# 3_SDRAM_Memories.net
KiCad netlist of a schematic drawn in Altium Designer
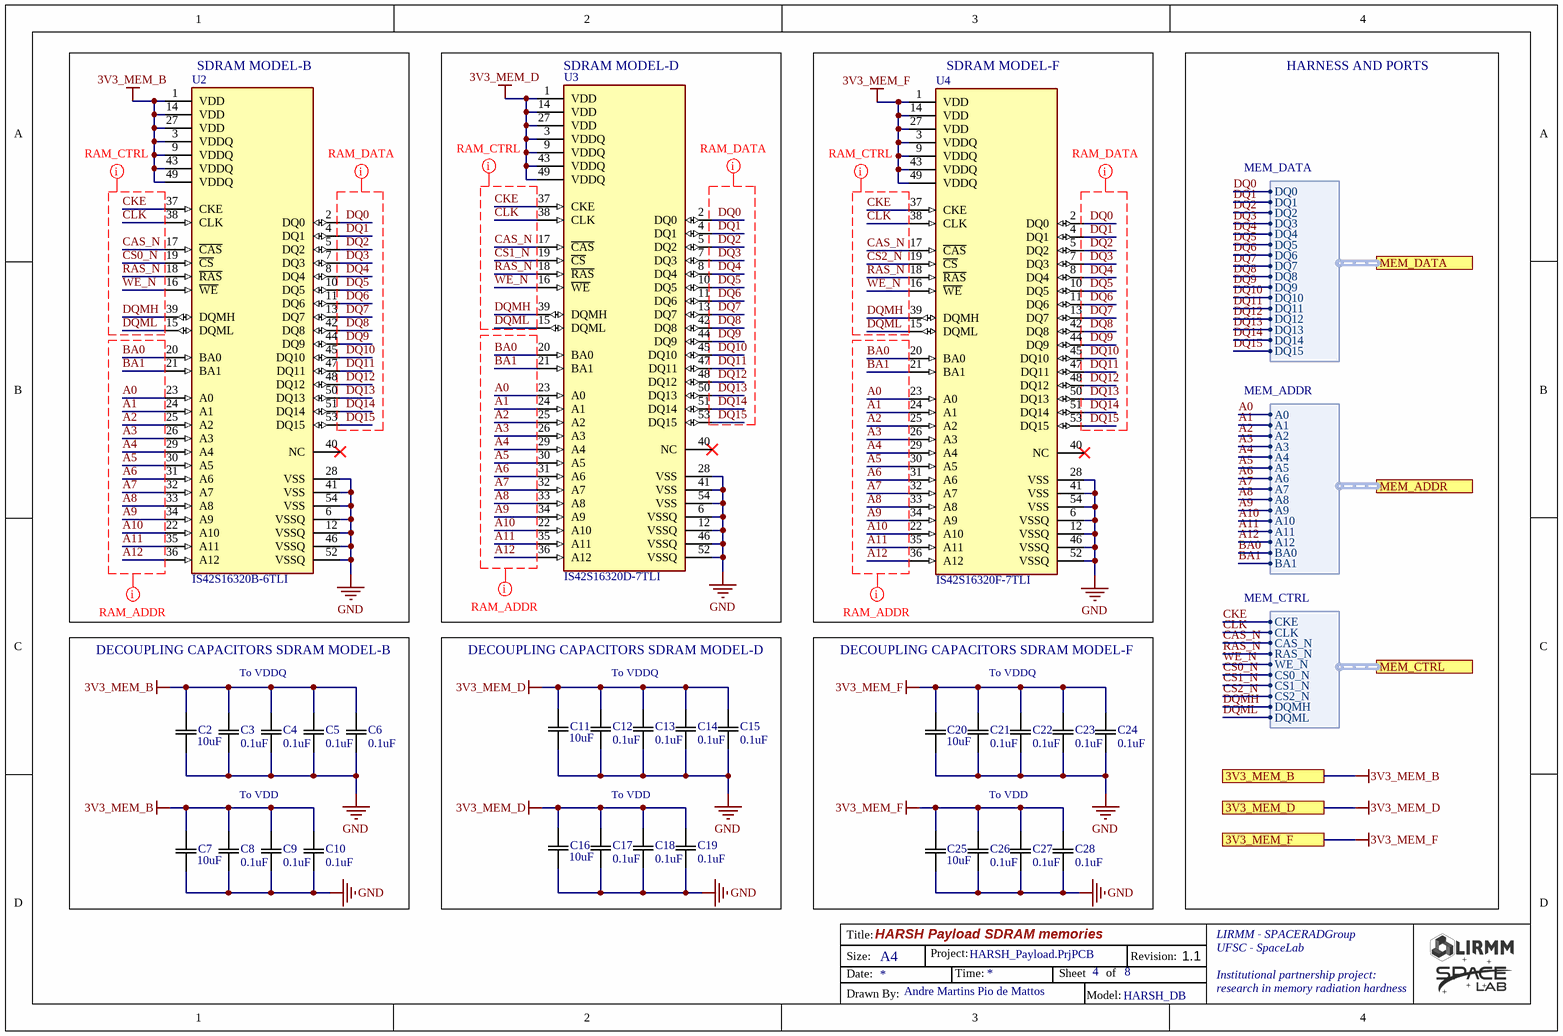
[diagram p0: 3_SDRAM_Memories.SchDoc]

(export (version "E")
  (design (tool "Eeschema 10.0.6"))
  (components
    (comp (ref "C2")
      (value "10uF")
      (footprint "DONE_C0603")
      (description "CAP CER 10uF 16V 0603 X5R")
      (fields
        (field (name "PARTNUMBER") "GRM188R61C106KAALD")
        (field (name "MANUFACTURER") "Murata")
        (field (name "CAPACITANCE") "10uF")
      )
      (libsource (lib "HARSH_Payload_SchLib") (part "DONE_CAP_10uF_0603_X5R"))
    )
    (comp (ref "C3")
      (value "100nF/50V")
      (footprint "DONE_C0603")
      (description "CAP CER 100nF 50V 0603 10%")
      (fields
        (field (name "PARTNUMBER") "C0603C104K5RAC3121")
        (field (name "MANUFACTURER") "Yageo")
        (field (name "CAPACITANCE") "0.1uF")
      )
      (libsource (lib "HARSH_Payload_SchLib") (part "DONE_CAP_0.1uF_0603_X7R"))
    )
    (comp (ref "C4")
      (value "100nF/50V")
      (footprint "DONE_C0603")
      (description "CAP CER 100nF 50V 0603 10%")
      (fields
        (field (name "PARTNUMBER") "C0603C104K5RAC3121")
        (field (name "MANUFACTURER") "Yageo")
        (field (name "CAPACITANCE") "0.1uF")
      )
      (libsource (lib "HARSH_Payload_SchLib") (part "DONE_CAP_0.1uF_0603_X7R"))
    )
    (comp (ref "C5")
      (value "100nF/50V")
      (footprint "DONE_C0603")
      (description "CAP CER 100nF 50V 0603 10%")
      (fields
        (field (name "PARTNUMBER") "C0603C104K5RAC3121")
        (field (name "MANUFACTURER") "Yageo")
        (field (name "CAPACITANCE") "0.1uF")
      )
      (libsource (lib "HARSH_Payload_SchLib") (part "DONE_CAP_0.1uF_0603_X7R"))
    )
    (comp (ref "C6")
      (value "100nF/50V")
      (footprint "DONE_C0603")
      (description "CAP CER 100nF 50V 0603 10%")
      (fields
        (field (name "PARTNUMBER") "C0603C104K5RAC3121")
        (field (name "MANUFACTURER") "Yageo")
        (field (name "CAPACITANCE") "0.1uF")
      )
      (libsource (lib "HARSH_Payload_SchLib") (part "DONE_CAP_0.1uF_0603_X7R"))
    )
    (comp (ref "C7")
      (value "10uF")
      (footprint "DONE_C0603")
      (description "CAP CER 10uF 16V 0603 X5R")
      (fields
        (field (name "PARTNUMBER") "GRM188R61C106KAALD")
        (field (name "MANUFACTURER") "Murata")
        (field (name "CAPACITANCE") "10uF")
      )
      (libsource (lib "HARSH_Payload_SchLib") (part "DONE_CAP_10uF_0603_X5R"))
    )
    (comp (ref "C8")
      (value "100nF/50V")
      (footprint "DONE_C0603")
      (description "CAP CER 100nF 50V 0603 10%")
      (fields
        (field (name "PARTNUMBER") "C0603C104K5RAC3121")
        (field (name "MANUFACTURER") "Yageo")
        (field (name "CAPACITANCE") "0.1uF")
      )
      (libsource (lib "HARSH_Payload_SchLib") (part "DONE_CAP_0.1uF_0603_X7R"))
    )
    (comp (ref "C9")
      (value "100nF/50V")
      (footprint "DONE_C0603")
      (description "CAP CER 100nF 50V 0603 10%")
      (fields
        (field (name "PARTNUMBER") "C0603C104K5RAC3121")
        (field (name "MANUFACTURER") "Yageo")
        (field (name "CAPACITANCE") "0.1uF")
      )
      (libsource (lib "HARSH_Payload_SchLib") (part "DONE_CAP_0.1uF_0603_X7R"))
    )
    (comp (ref "C10")
      (value "100nF/50V")
      (footprint "DONE_C0603")
      (description "CAP CER 100nF 50V 0603 10%")
      (fields
        (field (name "PARTNUMBER") "C0603C104K5RAC3121")
        (field (name "MANUFACTURER") "Yageo")
        (field (name "CAPACITANCE") "0.1uF")
      )
      (libsource (lib "HARSH_Payload_SchLib") (part "DONE_CAP_0.1uF_0603_X7R"))
    )
    (comp (ref "C11")
      (value "10uF")
      (footprint "DONE_C0603")
      (description "CAP CER 10uF 16V 0603 X5R")
      (fields
        (field (name "PARTNUMBER") "GRM188R61C106KAALD")
        (field (name "MANUFACTURER") "Murata")
        (field (name "CAPACITANCE") "10uF")
      )
      (libsource (lib "HARSH_Payload_SchLib") (part "DONE_CAP_10uF_0603_X5R"))
    )
    (comp (ref "C12")
      (value "100nF/50V")
      (footprint "DONE_C0603")
      (description "CAP CER 100nF 50V 0603 10%")
      (fields
        (field (name "PARTNUMBER") "C0603C104K5RAC3121")
        (field (name "MANUFACTURER") "Yageo")
        (field (name "CAPACITANCE") "0.1uF")
      )
      (libsource (lib "HARSH_Payload_SchLib") (part "DONE_CAP_0.1uF_0603_X7R"))
    )
    (comp (ref "C13")
      (value "100nF/50V")
      (footprint "DONE_C0603")
      (description "CAP CER 100nF 50V 0603 10%")
      (fields
        (field (name "PARTNUMBER") "C0603C104K5RAC3121")
        (field (name "MANUFACTURER") "Yageo")
        (field (name "CAPACITANCE") "0.1uF")
      )
      (libsource (lib "HARSH_Payload_SchLib") (part "DONE_CAP_0.1uF_0603_X7R"))
    )
    (comp (ref "C14")
      (value "100nF/50V")
      (footprint "DONE_C0603")
      (description "CAP CER 100nF 50V 0603 10%")
      (fields
        (field (name "PARTNUMBER") "C0603C104K5RAC3121")
        (field (name "MANUFACTURER") "Yageo")
        (field (name "CAPACITANCE") "0.1uF")
      )
      (libsource (lib "HARSH_Payload_SchLib") (part "DONE_CAP_0.1uF_0603_X7R"))
    )
    (comp (ref "C15")
      (value "100nF/50V")
      (footprint "DONE_C0603")
      (description "CAP CER 100nF 50V 0603 10%")
      (fields
        (field (name "PARTNUMBER") "C0603C104K5RAC3121")
        (field (name "MANUFACTURER") "Yageo")
        (field (name "CAPACITANCE") "0.1uF")
      )
      (libsource (lib "HARSH_Payload_SchLib") (part "DONE_CAP_0.1uF_0603_X7R"))
    )
    (comp (ref "C16")
      (value "10uF")
      (footprint "DONE_C0603")
      (description "CAP CER 10uF 16V 0603 X5R")
      (fields
        (field (name "PARTNUMBER") "GRM188R61C106KAALD")
        (field (name "MANUFACTURER") "Murata")
        (field (name "CAPACITANCE") "10uF")
      )
      (libsource (lib "HARSH_Payload_SchLib") (part "DONE_CAP_10uF_0603_X5R"))
    )
    (comp (ref "C17")
      (value "100nF/50V")
      (footprint "DONE_C0603")
      (description "CAP CER 100nF 50V 0603 10%")
      (fields
        (field (name "PARTNUMBER") "C0603C104K5RAC3121")
        (field (name "MANUFACTURER") "Yageo")
        (field (name "CAPACITANCE") "0.1uF")
      )
      (libsource (lib "HARSH_Payload_SchLib") (part "DONE_CAP_0.1uF_0603_X7R"))
    )
    (comp (ref "C18")
      (value "100nF/50V")
      (footprint "DONE_C0603")
      (description "CAP CER 100nF 50V 0603 10%")
      (fields
        (field (name "PARTNUMBER") "C0603C104K5RAC3121")
        (field (name "MANUFACTURER") "Yageo")
        (field (name "CAPACITANCE") "0.1uF")
      )
      (libsource (lib "HARSH_Payload_SchLib") (part "DONE_CAP_0.1uF_0603_X7R"))
    )
    (comp (ref "C19")
      (value "100nF/50V")
      (footprint "DONE_C0603")
      (description "CAP CER 100nF 50V 0603 10%")
      (fields
        (field (name "PARTNUMBER") "C0603C104K5RAC3121")
        (field (name "MANUFACTURER") "Yageo")
        (field (name "CAPACITANCE") "0.1uF")
      )
      (libsource (lib "HARSH_Payload_SchLib") (part "DONE_CAP_0.1uF_0603_X7R"))
    )
    (comp (ref "C20")
      (value "10uF")
      (footprint "DONE_C0603")
      (description "CAP CER 10uF 16V 0603 X5R")
      (fields
        (field (name "PARTNUMBER") "GRM188R61C106KAALD")
        (field (name "MANUFACTURER") "Murata")
        (field (name "CAPACITANCE") "10uF")
      )
      (libsource (lib "HARSH_Payload_SchLib") (part "DONE_CAP_10uF_0603_X5R"))
    )
    (comp (ref "C21")
      (value "100nF/50V")
      (footprint "DONE_C0603")
      (description "CAP CER 100nF 50V 0603 10%")
      (fields
        (field (name "PARTNUMBER") "C0603C104K5RAC3121")
        (field (name "MANUFACTURER") "Yageo")
        (field (name "CAPACITANCE") "0.1uF")
      )
      (libsource (lib "HARSH_Payload_SchLib") (part "DONE_CAP_0.1uF_0603_X7R"))
    )
    (comp (ref "C22")
      (value "100nF/50V")
      (footprint "DONE_C0603")
      (description "CAP CER 100nF 50V 0603 10%")
      (fields
        (field (name "PARTNUMBER") "C0603C104K5RAC3121")
        (field (name "MANUFACTURER") "Yageo")
        (field (name "CAPACITANCE") "0.1uF")
      )
      (libsource (lib "HARSH_Payload_SchLib") (part "DONE_CAP_0.1uF_0603_X7R"))
    )
    (comp (ref "C23")
      (value "100nF/50V")
      (footprint "DONE_C0603")
      (description "CAP CER 100nF 50V 0603 10%")
      (fields
        (field (name "PARTNUMBER") "C0603C104K5RAC3121")
        (field (name "MANUFACTURER") "Yageo")
        (field (name "CAPACITANCE") "0.1uF")
      )
      (libsource (lib "HARSH_Payload_SchLib") (part "DONE_CAP_0.1uF_0603_X7R"))
    )
    (comp (ref "C24")
      (value "100nF/50V")
      (footprint "DONE_C0603")
      (description "CAP CER 100nF 50V 0603 10%")
      (fields
        (field (name "PARTNUMBER") "C0603C104K5RAC3121")
        (field (name "MANUFACTURER") "Yageo")
        (field (name "CAPACITANCE") "0.1uF")
      )
      (libsource (lib "HARSH_Payload_SchLib") (part "DONE_CAP_0.1uF_0603_X7R"))
    )
    (comp (ref "C25")
      (value "10uF")
      (footprint "DONE_C0603")
      (description "CAP CER 10uF 16V 0603 X5R")
      (fields
        (field (name "PARTNUMBER") "GRM188R61C106KAALD")
        (field (name "MANUFACTURER") "Murata")
        (field (name "CAPACITANCE") "10uF")
      )
      (libsource (lib "HARSH_Payload_SchLib") (part "DONE_CAP_10uF_0603_X5R"))
    )
    (comp (ref "C26")
      (value "100nF/50V")
      (footprint "DONE_C0603")
      (description "CAP CER 100nF 50V 0603 10%")
      (fields
        (field (name "PARTNUMBER") "C0603C104K5RAC3121")
        (field (name "MANUFACTURER") "Yageo")
        (field (name "CAPACITANCE") "0.1uF")
      )
      (libsource (lib "HARSH_Payload_SchLib") (part "DONE_CAP_0.1uF_0603_X7R"))
    )
    (comp (ref "C27")
      (value "100nF/50V")
      (footprint "DONE_C0603")
      (description "CAP CER 100nF 50V 0603 10%")
      (fields
        (field (name "PARTNUMBER") "C0603C104K5RAC3121")
        (field (name "MANUFACTURER") "Yageo")
        (field (name "CAPACITANCE") "0.1uF")
      )
      (libsource (lib "HARSH_Payload_SchLib") (part "DONE_CAP_0.1uF_0603_X7R"))
    )
    (comp (ref "C28")
      (value "100nF/50V")
      (footprint "DONE_C0603")
      (description "CAP CER 100nF 50V 0603 10%")
      (fields
        (field (name "PARTNUMBER") "C0603C104K5RAC3121")
        (field (name "MANUFACTURER") "Yageo")
        (field (name "CAPACITANCE") "0.1uF")
      )
      (libsource (lib "HARSH_Payload_SchLib") (part "DONE_CAP_0.1uF_0603_X7R"))
    )
    (comp (ref "U2")
      (value "IS42S16320B-6TLI")
      (footprint "DONE_ISSI_MEM_TSOP_54")
      (description "DRAM 512M, 3.3V, SDRAM, 32Mx16, 143MHz, 54 pin TSOP II")
      (fields (field (name "PARTNUMBER") "IS42S16320B-6TLI"))
      (libsource (lib "HARSH_Payload_SchLib") (part "DONE_ISSI_MEM_MODEL_B"))
    )
    (comp (ref "U3")
      (value "IS42S16320D-7TLI")
      (footprint "DONE_ISSI_MEM_TSOP_54")
      (description "DRAM 512M, 3.3V, SDRAM, 32Mx16, 143MHz, 54 pin TSOP II")
      (fields (field (name "PARTNUMBER") "IS42S16320D-7TLI"))
      (libsource (lib "HARSH_Payload_SchLib") (part "DONE_ISSI_MEM_MODEL_D"))
    )
    (comp (ref "U4")
      (value "IS42S16320F-7TLI")
      (footprint "DONE_ISSI_MEM_TSOP_54")
      (description "DRAM 512M, 3.3V, SDRAM, 32Mx16, 143MHz, 54 pin TSOP II")
      (fields (field (name "PARTNUMBER") "IS42S16320F-7TLI"))
      (libsource (lib "HARSH_Payload_SchLib") (part "DONE_ISSI_MEM_MODEL_F"))
    )
  )
  (nets
    (net (code "4") (name "/A0") (class "Default")
      (node (ref "U2") (pin "23") (pinfunction "A0_23") (pintype "input"))
      (node (ref "U3") (pin "23") (pinfunction "A0_23") (pintype "input"))
      (node (ref "U4") (pin "23") (pinfunction "A0_23") (pintype "input"))
    )
    (net (code "5") (name "/A1") (class "Default")
      (node (ref "U2") (pin "24") (pinfunction "A1_24") (pintype "input"))
      (node (ref "U3") (pin "24") (pinfunction "A1_24") (pintype "input"))
      (node (ref "U4") (pin "24") (pinfunction "A1_24") (pintype "input"))
    )
    (net (code "6") (name "/A2") (class "Default")
      (node (ref "U2") (pin "25") (pinfunction "A2_25") (pintype "input"))
      (node (ref "U3") (pin "25") (pinfunction "A2_25") (pintype "input"))
      (node (ref "U4") (pin "25") (pinfunction "A2_25") (pintype "input"))
    )
    (net (code "7") (name "/A3") (class "Default")
      (node (ref "U2") (pin "26") (pinfunction "A3_26") (pintype "input"))
      (node (ref "U3") (pin "26") (pinfunction "A3_26") (pintype "input"))
      (node (ref "U4") (pin "26") (pinfunction "A3_26") (pintype "input"))
    )
    (net (code "8") (name "/A4") (class "Default")
      (node (ref "U2") (pin "29") (pinfunction "A4_29") (pintype "input"))
      (node (ref "U3") (pin "29") (pinfunction "A4_29") (pintype "input"))
      (node (ref "U4") (pin "29") (pinfunction "A4_29") (pintype "input"))
    )
    (net (code "9") (name "/A5") (class "Default")
      (node (ref "U2") (pin "30") (pinfunction "A5_30") (pintype "input"))
      (node (ref "U3") (pin "30") (pinfunction "A5_30") (pintype "input"))
      (node (ref "U4") (pin "30") (pinfunction "A5_30") (pintype "input"))
    )
    (net (code "10") (name "/A6") (class "Default")
      (node (ref "U2") (pin "31") (pinfunction "A6_31") (pintype "input"))
      (node (ref "U3") (pin "31") (pinfunction "A6_31") (pintype "input"))
      (node (ref "U4") (pin "31") (pinfunction "A6_31") (pintype "input"))
    )
    (net (code "11") (name "/A7") (class "Default")
      (node (ref "U2") (pin "32") (pinfunction "A7_32") (pintype "input"))
      (node (ref "U3") (pin "32") (pinfunction "A7_32") (pintype "input"))
      (node (ref "U4") (pin "32") (pinfunction "A7_32") (pintype "input"))
    )
    (net (code "12") (name "/A8") (class "Default")
      (node (ref "U2") (pin "33") (pinfunction "A8_33") (pintype "input"))
      (node (ref "U3") (pin "33") (pinfunction "A8_33") (pintype "input"))
      (node (ref "U4") (pin "33") (pinfunction "A8_33") (pintype "input"))
    )
    (net (code "13") (name "/A9") (class "Default")
      (node (ref "U2") (pin "34") (pinfunction "A9_34") (pintype "input"))
      (node (ref "U3") (pin "34") (pinfunction "A9_34") (pintype "input"))
      (node (ref "U4") (pin "34") (pinfunction "A9_34") (pintype "input"))
    )
    (net (code "14") (name "/A10") (class "Default")
      (node (ref "U2") (pin "22") (pinfunction "A10_22") (pintype "input"))
      (node (ref "U3") (pin "22") (pinfunction "A10_22") (pintype "input"))
      (node (ref "U4") (pin "22") (pinfunction "A10_22") (pintype "input"))
    )
    (net (code "15") (name "/A11") (class "Default")
      (node (ref "U2") (pin "35") (pinfunction "A11_35") (pintype "input"))
      (node (ref "U3") (pin "35") (pinfunction "A11_35") (pintype "input"))
      (node (ref "U4") (pin "35") (pinfunction "A11_35") (pintype "input"))
    )
    (net (code "16") (name "/A12") (class "Default")
      (node (ref "U2") (pin "36") (pinfunction "A12_36") (pintype "input"))
      (node (ref "U3") (pin "36") (pinfunction "A12_36") (pintype "input"))
      (node (ref "U4") (pin "36") (pinfunction "A12_36") (pintype "input"))
    )
    (net (code "17") (name "/BA0") (class "Default")
      (node (ref "U2") (pin "20") (pinfunction "BA0_20") (pintype "input"))
      (node (ref "U3") (pin "20") (pinfunction "BA0_20") (pintype "input"))
      (node (ref "U4") (pin "20") (pinfunction "BA0_20") (pintype "input"))
    )
    (net (code "18") (name "/BA1") (class "Default")
      (node (ref "U2") (pin "21") (pinfunction "BA1_21") (pintype "input"))
      (node (ref "U3") (pin "21") (pinfunction "BA1_21") (pintype "input"))
      (node (ref "U4") (pin "21") (pinfunction "BA1_21") (pintype "input"))
    )
    (net (code "19") (name "/CAS_N") (class "Default")
      (node (ref "U2") (pin "17") (pinfunction "~{CAS}_17") (pintype "input"))
      (node (ref "U3") (pin "17") (pinfunction "~{CAS}_17") (pintype "input"))
      (node (ref "U4") (pin "17") (pinfunction "~{CAS}_17") (pintype "input"))
    )
    (net (code "20") (name "/CKE") (class "Default")
      (node (ref "U2") (pin "37") (pinfunction "CKE_37") (pintype "input"))
      (node (ref "U3") (pin "37") (pinfunction "CKE_37") (pintype "input"))
      (node (ref "U4") (pin "37") (pinfunction "CKE_37") (pintype "input"))
    )
    (net (code "21") (name "/CLK") (class "Default")
      (node (ref "U2") (pin "38") (pinfunction "CLK_38") (pintype "input"))
      (node (ref "U3") (pin "38") (pinfunction "CLK_38") (pintype "input"))
      (node (ref "U4") (pin "38") (pinfunction "CLK_38") (pintype "input"))
    )
    (net (code "22") (name "/CS0_N") (class "Default")
      (node (ref "U2") (pin "19") (pinfunction "~{CS}_19") (pintype "input"))
    )
    (net (code "23") (name "/CS1_N") (class "Default")
      (node (ref "U3") (pin "19") (pinfunction "~{CS}_19") (pintype "input"))
    )
    (net (code "24") (name "/CS2_N") (class "Default")
      (node (ref "U4") (pin "19") (pinfunction "~{CS}_19") (pintype "input"))
    )
    (net (code "25") (name "/DQ0") (class "Default")
      (node (ref "U2") (pin "2") (pinfunction "DQ0_2") (pintype "bidirectional"))
      (node (ref "U3") (pin "2") (pinfunction "DQ0_2") (pintype "bidirectional"))
      (node (ref "U4") (pin "2") (pinfunction "DQ0_2") (pintype "bidirectional"))
    )
    (net (code "26") (name "/DQ1") (class "Default")
      (node (ref "U2") (pin "4") (pinfunction "DQ1_4") (pintype "bidirectional"))
      (node (ref "U3") (pin "4") (pinfunction "DQ1_4") (pintype "bidirectional"))
      (node (ref "U4") (pin "4") (pinfunction "DQ1_4") (pintype "bidirectional"))
    )
    (net (code "27") (name "/DQ2") (class "Default")
      (node (ref "U2") (pin "5") (pinfunction "DQ2_5") (pintype "bidirectional"))
      (node (ref "U3") (pin "5") (pinfunction "DQ2_5") (pintype "bidirectional"))
      (node (ref "U4") (pin "5") (pinfunction "DQ2_5") (pintype "bidirectional"))
    )
    (net (code "28") (name "/DQ3") (class "Default")
      (node (ref "U2") (pin "7") (pinfunction "DQ3_7") (pintype "bidirectional"))
      (node (ref "U3") (pin "7") (pinfunction "DQ3_7") (pintype "bidirectional"))
      (node (ref "U4") (pin "7") (pinfunction "DQ3_7") (pintype "bidirectional"))
    )
    (net (code "29") (name "/DQ4") (class "Default")
      (node (ref "U2") (pin "8") (pinfunction "DQ4_8") (pintype "bidirectional"))
      (node (ref "U3") (pin "8") (pinfunction "DQ4_8") (pintype "bidirectional"))
      (node (ref "U4") (pin "8") (pinfunction "DQ4_8") (pintype "bidirectional"))
    )
    (net (code "30") (name "/DQ5") (class "Default")
      (node (ref "U2") (pin "10") (pinfunction "DQ5_10") (pintype "bidirectional"))
      (node (ref "U3") (pin "10") (pinfunction "DQ5_10") (pintype "bidirectional"))
      (node (ref "U4") (pin "10") (pinfunction "DQ5_10") (pintype "bidirectional"))
    )
    (net (code "31") (name "/DQ6") (class "Default")
      (node (ref "U2") (pin "11") (pinfunction "DQ6_11") (pintype "bidirectional"))
      (node (ref "U3") (pin "11") (pinfunction "DQ6_11") (pintype "bidirectional"))
      (node (ref "U4") (pin "11") (pinfunction "DQ6_11") (pintype "bidirectional"))
    )
    (net (code "32") (name "/DQ7") (class "Default")
      (node (ref "U2") (pin "13") (pinfunction "DQ7_13") (pintype "bidirectional"))
      (node (ref "U3") (pin "13") (pinfunction "DQ7_13") (pintype "bidirectional"))
      (node (ref "U4") (pin "13") (pinfunction "DQ7_13") (pintype "bidirectional"))
    )
    (net (code "33") (name "/DQ8") (class "Default")
      (node (ref "U2") (pin "42") (pinfunction "DQ8_42") (pintype "bidirectional"))
      (node (ref "U3") (pin "42") (pinfunction "DQ8_42") (pintype "bidirectional"))
      (node (ref "U4") (pin "42") (pinfunction "DQ8_42") (pintype "bidirectional"))
    )
    (net (code "34") (name "/DQ9") (class "Default")
      (node (ref "U2") (pin "44") (pinfunction "DQ9_44") (pintype "bidirectional"))
      (node (ref "U3") (pin "44") (pinfunction "DQ9_44") (pintype "bidirectional"))
      (node (ref "U4") (pin "44") (pinfunction "DQ9_44") (pintype "bidirectional"))
    )
    (net (code "35") (name "/DQ10") (class "Default")
      (node (ref "U2") (pin "45") (pinfunction "DQ10_45") (pintype "bidirectional"))
      (node (ref "U3") (pin "45") (pinfunction "DQ10_45") (pintype "bidirectional"))
      (node (ref "U4") (pin "45") (pinfunction "DQ10_45") (pintype "bidirectional"))
    )
    (net (code "36") (name "/DQ11") (class "Default")
      (node (ref "U2") (pin "47") (pinfunction "DQ11_47") (pintype "bidirectional"))
      (node (ref "U3") (pin "47") (pinfunction "DQ11_47") (pintype "bidirectional"))
      (node (ref "U4") (pin "47") (pinfunction "DQ11_47") (pintype "bidirectional"))
    )
    (net (code "37") (name "/DQ12") (class "Default")
      (node (ref "U2") (pin "48") (pinfunction "DQ12_48") (pintype "bidirectional"))
      (node (ref "U3") (pin "48") (pinfunction "DQ12_48") (pintype "bidirectional"))
      (node (ref "U4") (pin "48") (pinfunction "DQ12_48") (pintype "bidirectional"))
    )
    (net (code "38") (name "/DQ13") (class "Default")
      (node (ref "U2") (pin "50") (pinfunction "DQ13_50") (pintype "bidirectional"))
      (node (ref "U3") (pin "50") (pinfunction "DQ13_50") (pintype "bidirectional"))
      (node (ref "U4") (pin "50") (pinfunction "DQ13_50") (pintype "bidirectional"))
    )
    (net (code "39") (name "/DQ14") (class "Default")
      (node (ref "U2") (pin "51") (pinfunction "DQ14_51") (pintype "bidirectional"))
      (node (ref "U3") (pin "51") (pinfunction "DQ14_51") (pintype "bidirectional"))
      (node (ref "U4") (pin "51") (pinfunction "DQ14_51") (pintype "bidirectional"))
    )
    (net (code "40") (name "/DQ15") (class "Default")
      (node (ref "U2") (pin "53") (pinfunction "DQ15_53") (pintype "bidirectional"))
      (node (ref "U3") (pin "53") (pinfunction "DQ15_53") (pintype "bidirectional"))
      (node (ref "U4") (pin "53") (pinfunction "DQ15_53") (pintype "bidirectional"))
    )
    (net (code "41") (name "/DQMH") (class "Default")
      (node (ref "U2") (pin "39") (pinfunction "DQMH_39") (pintype "bidirectional"))
      (node (ref "U3") (pin "39") (pinfunction "DQMH_39") (pintype "bidirectional"))
      (node (ref "U4") (pin "39") (pinfunction "DQMH_39") (pintype "bidirectional"))
    )
    (net (code "42") (name "/DQML") (class "Default")
      (node (ref "U2") (pin "15") (pinfunction "DQML_15") (pintype "bidirectional"))
      (node (ref "U3") (pin "15") (pinfunction "DQML_15") (pintype "bidirectional"))
      (node (ref "U4") (pin "15") (pinfunction "DQML_15") (pintype "bidirectional"))
    )
    (net (code "43") (name "/RAS_N") (class "Default")
      (node (ref "U2") (pin "18") (pinfunction "~{RAS}_18") (pintype "input"))
      (node (ref "U3") (pin "18") (pinfunction "~{RAS}_18") (pintype "input"))
      (node (ref "U4") (pin "18") (pinfunction "~{RAS}_18") (pintype "input"))
    )
    (net (code "44") (name "/WE_N") (class "Default")
      (node (ref "U2") (pin "16") (pinfunction "~{WE}_16") (pintype "input"))
      (node (ref "U3") (pin "16") (pinfunction "~{WE}_16") (pintype "input"))
      (node (ref "U4") (pin "16") (pinfunction "~{WE}_16") (pintype "input"))
    )
    (net (code "48") (name "3V3_MEM_B") (class "Default")
      (node (ref "C10") (pin "1") (pinfunction "1_1") (pintype "passive"))
      (node (ref "C2") (pin "1") (pinfunction "1_1") (pintype "passive"))
      (node (ref "C3") (pin "1") (pinfunction "1_1") (pintype "passive"))
      (node (ref "C4") (pin "1") (pinfunction "1_1") (pintype "passive"))
      (node (ref "C5") (pin "1") (pinfunction "1_1") (pintype "passive"))
      (node (ref "C6") (pin "1") (pinfunction "1_1") (pintype "passive"))
      (node (ref "C7") (pin "1") (pinfunction "1_1") (pintype "passive"))
      (node (ref "C8") (pin "1") (pinfunction "1_1") (pintype "passive"))
      (node (ref "C9") (pin "1") (pinfunction "1_1") (pintype "passive"))
      (node (ref "U2") (pin "1") (pinfunction "VDD_1") (pintype "power_in"))
      (node (ref "U2") (pin "14") (pinfunction "VDD_14") (pintype "power_in"))
      (node (ref "U2") (pin "27") (pinfunction "VDD_27") (pintype "power_in"))
      (node (ref "U2") (pin "3") (pinfunction "VDDQ_3") (pintype "power_in"))
      (node (ref "U2") (pin "43") (pinfunction "VDDQ_43") (pintype "power_in"))
      (node (ref "U2") (pin "49") (pinfunction "VDDQ_49") (pintype "power_in"))
      (node (ref "U2") (pin "9") (pinfunction "VDDQ_9") (pintype "power_in"))
    )
    (net (code "49") (name "3V3_MEM_D") (class "Default")
      (node (ref "C11") (pin "1") (pinfunction "1_1") (pintype "passive"))
      (node (ref "C12") (pin "1") (pinfunction "1_1") (pintype "passive"))
      (node (ref "C13") (pin "1") (pinfunction "1_1") (pintype "passive"))
      (node (ref "C14") (pin "1") (pinfunction "1_1") (pintype "passive"))
      (node (ref "C15") (pin "1") (pinfunction "1_1") (pintype "passive"))
      (node (ref "C16") (pin "1") (pinfunction "1_1") (pintype "passive"))
      (node (ref "C17") (pin "1") (pinfunction "1_1") (pintype "passive"))
      (node (ref "C18") (pin "1") (pinfunction "1_1") (pintype "passive"))
      (node (ref "C19") (pin "1") (pinfunction "1_1") (pintype "passive"))
      (node (ref "U3") (pin "1") (pinfunction "VDD_1") (pintype "power_in"))
      (node (ref "U3") (pin "14") (pinfunction "VDD_14") (pintype "power_in"))
      (node (ref "U3") (pin "27") (pinfunction "VDD_27") (pintype "power_in"))
      (node (ref "U3") (pin "3") (pinfunction "VDDQ_3") (pintype "power_in"))
      (node (ref "U3") (pin "43") (pinfunction "VDDQ_43") (pintype "power_in"))
      (node (ref "U3") (pin "49") (pinfunction "VDDQ_49") (pintype "power_in"))
      (node (ref "U3") (pin "9") (pinfunction "VDDQ_9") (pintype "power_in"))
    )
    (net (code "50") (name "3V3_MEM_F") (class "Default")
      (node (ref "C20") (pin "1") (pinfunction "1_1") (pintype "passive"))
      (node (ref "C21") (pin "1") (pinfunction "1_1") (pintype "passive"))
      (node (ref "C22") (pin "1") (pinfunction "1_1") (pintype "passive"))
      (node (ref "C23") (pin "1") (pinfunction "1_1") (pintype "passive"))
      (node (ref "C24") (pin "1") (pinfunction "1_1") (pintype "passive"))
      (node (ref "C25") (pin "1") (pinfunction "1_1") (pintype "passive"))
      (node (ref "C26") (pin "1") (pinfunction "1_1") (pintype "passive"))
      (node (ref "C27") (pin "1") (pinfunction "1_1") (pintype "passive"))
      (node (ref "C28") (pin "1") (pinfunction "1_1") (pintype "passive"))
      (node (ref "U4") (pin "1") (pinfunction "VDD_1") (pintype "power_in"))
      (node (ref "U4") (pin "14") (pinfunction "VDD_14") (pintype "power_in"))
      (node (ref "U4") (pin "27") (pinfunction "VDD_27") (pintype "power_in"))
      (node (ref "U4") (pin "3") (pinfunction "VDDQ_3") (pintype "power_in"))
      (node (ref "U4") (pin "43") (pinfunction "VDDQ_43") (pintype "power_in"))
      (node (ref "U4") (pin "49") (pinfunction "VDDQ_49") (pintype "power_in"))
      (node (ref "U4") (pin "9") (pinfunction "VDDQ_9") (pintype "power_in"))
    )
    (net (code "51") (name "GND") (class "Default")
      (node (ref "C10") (pin "2") (pinfunction "2_2") (pintype "passive"))
      (node (ref "C11") (pin "2") (pinfunction "2_2") (pintype "passive"))
      (node (ref "C12") (pin "2") (pinfunction "2_2") (pintype "passive"))
      (node (ref "C13") (pin "2") (pinfunction "2_2") (pintype "passive"))
      (node (ref "C14") (pin "2") (pinfunction "2_2") (pintype "passive"))
      (node (ref "C15") (pin "2") (pinfunction "2_2") (pintype "passive"))
      (node (ref "C16") (pin "2") (pinfunction "2_2") (pintype "passive"))
      (node (ref "C17") (pin "2") (pinfunction "2_2") (pintype "passive"))
      (node (ref "C18") (pin "2") (pinfunction "2_2") (pintype "passive"))
      (node (ref "C19") (pin "2") (pinfunction "2_2") (pintype "passive"))
      (node (ref "C2") (pin "2") (pinfunction "2_2") (pintype "passive"))
      (node (ref "C20") (pin "2") (pinfunction "2_2") (pintype "passive"))
      (node (ref "C21") (pin "2") (pinfunction "2_2") (pintype "passive"))
      (node (ref "C22") (pin "2") (pinfunction "2_2") (pintype "passive"))
      (node (ref "C23") (pin "2") (pinfunction "2_2") (pintype "passive"))
      (node (ref "C24") (pin "2") (pinfunction "2_2") (pintype "passive"))
      (node (ref "C25") (pin "2") (pinfunction "2_2") (pintype "passive"))
      (node (ref "C26") (pin "2") (pinfunction "2_2") (pintype "passive"))
      (node (ref "C27") (pin "2") (pinfunction "2_2") (pintype "passive"))
      (node (ref "C28") (pin "2") (pinfunction "2_2") (pintype "passive"))
      (node (ref "C3") (pin "2") (pinfunction "2_2") (pintype "passive"))
      (node (ref "C4") (pin "2") (pinfunction "2_2") (pintype "passive"))
      (node (ref "C5") (pin "2") (pinfunction "2_2") (pintype "passive"))
      (node (ref "C6") (pin "2") (pinfunction "2_2") (pintype "passive"))
      (node (ref "C7") (pin "2") (pinfunction "2_2") (pintype "passive"))
      (node (ref "C8") (pin "2") (pinfunction "2_2") (pintype "passive"))
      (node (ref "C9") (pin "2") (pinfunction "2_2") (pintype "passive"))
      (node (ref "U2") (pin "12") (pinfunction "VSSQ_12") (pintype "power_in"))
      (node (ref "U2") (pin "28") (pinfunction "VSS_28") (pintype "power_in"))
      (node (ref "U2") (pin "41") (pinfunction "VSS_41") (pintype "power_in"))
      (node (ref "U2") (pin "46") (pinfunction "VSSQ_46") (pintype "power_in"))
      (node (ref "U2") (pin "52") (pinfunction "VSSQ_52") (pintype "power_in"))
      (node (ref "U2") (pin "54") (pinfunction "VSS_54") (pintype "power_in"))
      (node (ref "U2") (pin "6") (pinfunction "VSSQ_6") (pintype "power_in"))
      (node (ref "U3") (pin "12") (pinfunction "VSSQ_12") (pintype "power_in"))
      (node (ref "U3") (pin "28") (pinfunction "VSS_28") (pintype "power_in"))
      (node (ref "U3") (pin "41") (pinfunction "VSS_41") (pintype "power_in"))
      (node (ref "U3") (pin "46") (pinfunction "VSSQ_46") (pintype "power_in"))
      (node (ref "U3") (pin "52") (pinfunction "VSSQ_52") (pintype "power_in"))
      (node (ref "U3") (pin "54") (pinfunction "VSS_54") (pintype "power_in"))
      (node (ref "U3") (pin "6") (pinfunction "VSSQ_6") (pintype "power_in"))
      (node (ref "U4") (pin "12") (pinfunction "VSSQ_12") (pintype "power_in"))
      (node (ref "U4") (pin "28") (pinfunction "VSS_28") (pintype "power_in"))
      (node (ref "U4") (pin "41") (pinfunction "VSS_41") (pintype "power_in"))
      (node (ref "U4") (pin "46") (pinfunction "VSSQ_46") (pintype "power_in"))
      (node (ref "U4") (pin "52") (pinfunction "VSSQ_52") (pintype "power_in"))
      (node (ref "U4") (pin "54") (pinfunction "VSS_54") (pintype "power_in"))
      (node (ref "U4") (pin "6") (pinfunction "VSSQ_6") (pintype "power_in"))
    )
    (net (code "52") (name "unconnected-(U2-NC-Pad40)") (class "Default")
      (node (ref "U2") (pin "40") (pinfunction "NC_40") (pintype "passive+no_connect"))
    )
    (net (code "53") (name "unconnected-(U3-NC-Pad40)") (class "Default")
      (node (ref "U3") (pin "40") (pinfunction "NC_40") (pintype "passive+no_connect"))
    )
    (net (code "54") (name "unconnected-(U4-NC-Pad40)") (class "Default")
      (node (ref "U4") (pin "40") (pinfunction "NC_40") (pintype "passive+no_connect"))
    )
  )
)
